# GSM.net
KiCad netlist of a schematic drawn in Altium Designer
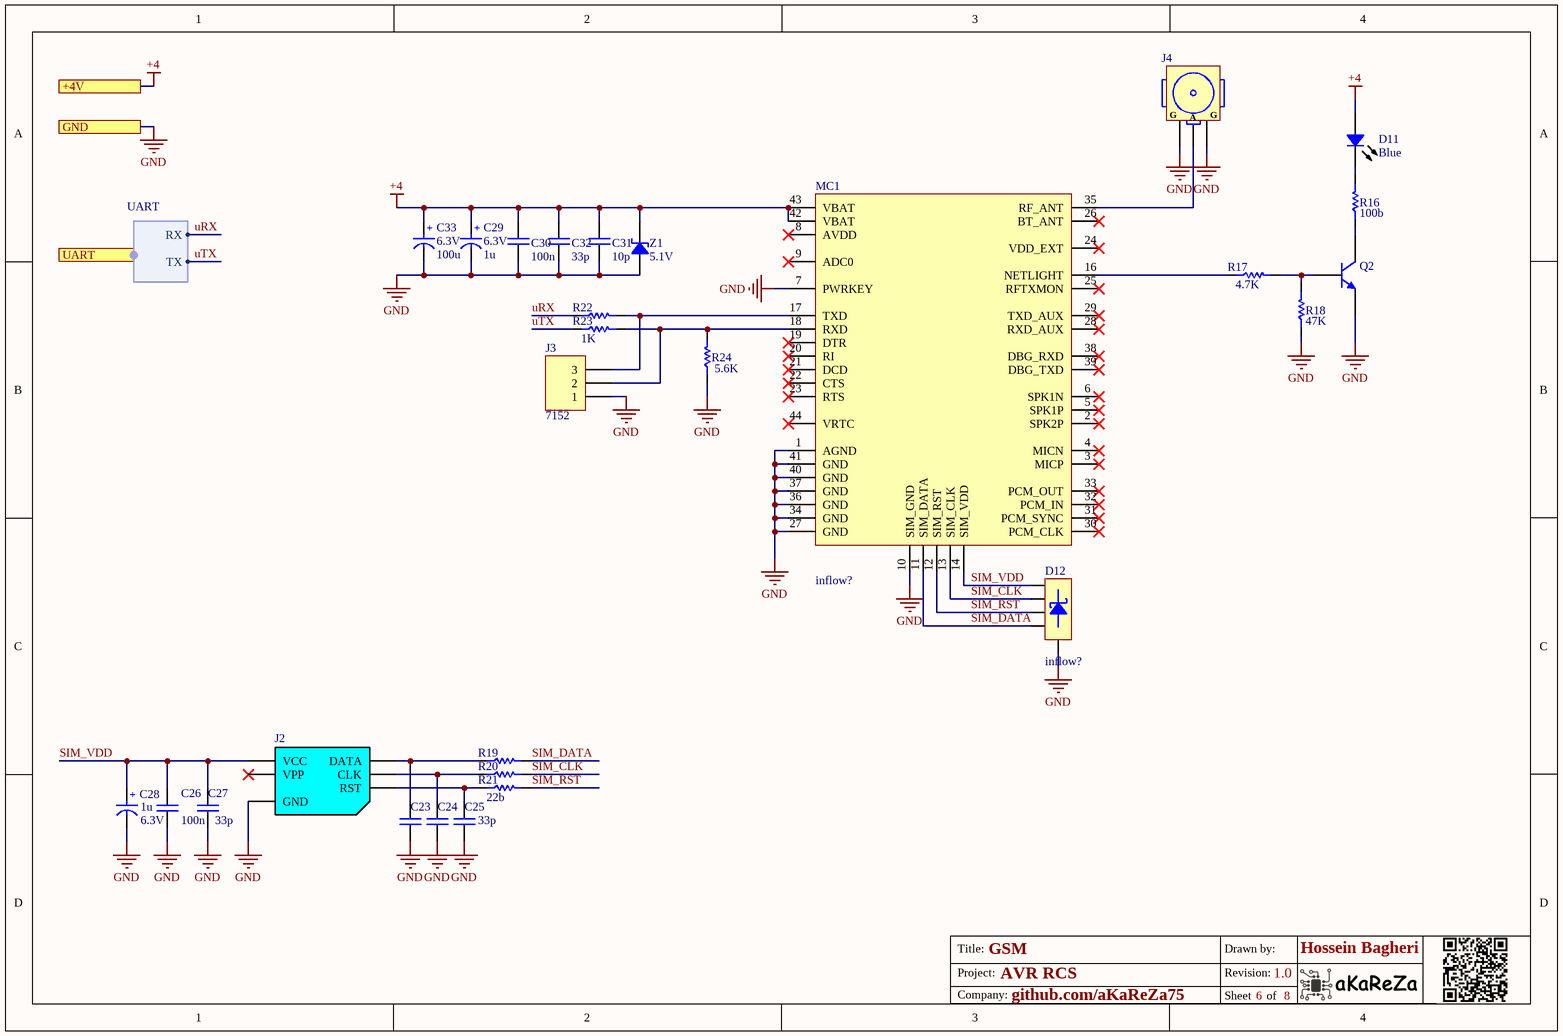
[diagram p0: GSM.SchDoc]

(export (version "E")
  (design (tool "Eeschema 10.0.6"))
  (components
    (comp (ref "C23")
      (value "33p")
      (footprint "CAP 0805/2012")
      (description "Bipolar ceramic capacitor SMD")
      (libsource (lib "aKaReZa") (part "Cap_Multi_SMD_0805"))
    )
    (comp (ref "C24")
      (value "33p")
      (footprint "CAP 0805/2012")
      (description "Bipolar ceramic capacitor SMD")
      (libsource (lib "aKaReZa") (part "Cap_Multi_SMD_0805"))
    )
    (comp (ref "C25")
      (value "33p")
      (footprint "CAP 0805/2012")
      (description "Bipolar ceramic capacitor SMD")
      (libsource (lib "aKaReZa") (part "Cap_Multi_SMD_0805"))
    )
    (comp (ref "C26")
      (value "100n")
      (footprint "CAP 0805/2012")
      (description "Bipolar ceramic capacitor SMD")
      (libsource (lib "aKaReZa") (part "Cap_Multi_SMD_100nF_0805"))
    )
    (comp (ref "C27")
      (value "33p")
      (footprint "CAP 0805/2012")
      (description "Bipolar ceramic capacitor SMD")
      (libsource (lib "aKaReZa") (part "Cap_Multi_SMD_0805"))
    )
    (comp (ref "C28")
      (value "1u")
      (footprint "SMT_C_Tantalum_A")
      (description "Tantalum Capacitor,TAJ Series-SMD")
      (fields (field (name "RATING") "6.3V"))
      (libsource (lib "aKaReZa") (part "Cap_Tantalum"))
    )
    (comp (ref "C29")
      (value "1u")
      (footprint "SMT_C_Tantalum_A")
      (description "Tantalum Capacitor,TAJ Series-SMD")
      (fields (field (name "RATING") "6.3V"))
      (libsource (lib "aKaReZa") (part "Cap_Tantalum"))
    )
    (comp (ref "C30")
      (value "100n")
      (footprint "CAP 1206/3216")
      (description "Bipolar ceramic capacitor SMD")
      (libsource (lib "aKaReZa") (part "Cap_Multi_SMD_100nF_1206"))
    )
    (comp (ref "C31")
      (value "10p")
      (footprint "CAP 1206/3216")
      (description "Bipolar ceramic capacitor SMD")
      (libsource (lib "aKaReZa") (part "Cap_Multi_SMD_1206"))
    )
    (comp (ref "C32")
      (value "33p")
      (footprint "CAP 1206/3216")
      (description "Bipolar ceramic capacitor SMD")
      (libsource (lib "aKaReZa") (part "Cap_Multi_SMD_1206"))
    )
    (comp (ref "C33")
      (value "100u")
      (footprint "SMT_C_Tantalum_C")
      (description "Tantalum Capacitor,TAJ Series-SMD")
      (fields (field (name "RATING") "6.3V"))
      (libsource (lib "aKaReZa") (part "Cap_Tantalum"))
    )
    (comp (ref "D11")
      (value "Blue")
      (footprint "LED 0805/2012 BLUE")
      (description "LED")
      (fields (field (name "VALIDATION") "Valid"))
      (libsource (lib "aKaReZa") (part "Semi_LED_SMD"))
    )
    (comp (ref "D12")
      (value "SMF-05")
      (footprint "SC70-5_N")
      (description "TVS Diode Array")
      (fields (field (name "INFLOW") "inflow?") (field (name "VALIDATION") "Valid"))
      (libsource (lib "aKaReZa") (part "Semi_Diod_TVS_SMF05"))
    )
    (comp (ref "J2")
      (value "6'Pin")
      (footprint "GCT_SIM8051_Plastik")
      (description "Nano SimCard Holder 6P")
      (fields (field (name "VALIDATION") "Valid"))
      (libsource (lib "aKaReZa") (part "Con_Socket_SimCard_1"))
    )
    (comp (ref "J3")
      (value "3")
      (footprint "HDR_THT_3M_2.54mm")
      (description "Header, single row, 3 pin")
      (fields (field (name "INFLOW") "7152") (field (name "VALIDATION") "NT"))
      (libsource (lib "aKaReZa") (part "Con_MPH_3x1_V_THT_2.54"))
    )
    (comp (ref "J4") (value "U.FL") (footprint "IPEX-3x3mm") (libsource (lib "aKaReZa") (part "Con_RF_U.FL")))
    (comp (ref "MC1")
      (value "M66")
      (footprint "m66")
      (description "Quectel GSM/GPRS Module")
      (fields (field (name "INFLOW") "inflow?") (field (name "VALIDATION") "Valid"))
      (libsource (lib "aKaReZa") (part "ModSen_Com_M66"))
    )
    (comp (ref "Q2")
      (value "NPN")
      (footprint "SOT23_N")
      (description "NPN General purpose Transistor")
      (fields (field (name "VALIDATION") "Valid"))
      (libsource (lib "aKaReZa") (part "Semi_BJT_BC817"))
    )
    (comp (ref "R16")
      (value "100b")
      (footprint "RES 0805 (2012X06L)")
      (description "Resistor")
      (libsource (lib "aKaReZa") (part "Res_SMD_0805"))
    )
    (comp (ref "R17")
      (value "4.7K")
      (footprint "RES 0805 (2012X06L)")
      (description "Resistor")
      (libsource (lib "aKaReZa") (part "Res_SMD_0805"))
    )
    (comp (ref "R18")
      (value "47K")
      (footprint "RES 0805 (2012X06L)")
      (description "Resistor")
      (libsource (lib "aKaReZa") (part "Res_SMD_0805"))
    )
    (comp (ref "R19")
      (value "22b")
      (footprint "RES 0805 (2012X06L)")
      (description "Resistor")
      (libsource (lib "aKaReZa") (part "Res_SMD_0805"))
    )
    (comp (ref "R20")
      (value "22b")
      (footprint "RES 0805 (2012X06L)")
      (description "Resistor")
      (libsource (lib "aKaReZa") (part "Res_SMD_0805"))
    )
    (comp (ref "R21")
      (value "22b")
      (footprint "RES 0805 (2012X06L)")
      (description "Resistor")
      (libsource (lib "aKaReZa") (part "Res_SMD_0805"))
    )
    (comp (ref "R22")
      (value "1K")
      (footprint "RES 0805 (2012X06L)")
      (description "Resistor")
      (libsource (lib "aKaReZa") (part "Res_SMD_0805"))
    )
    (comp (ref "R23")
      (value "1K")
      (footprint "RES 0805 (2012X06L)")
      (description "Resistor")
      (libsource (lib "aKaReZa") (part "Res_SMD_0805"))
    )
    (comp (ref "R24")
      (value "5.6K")
      (footprint "RES 0805 (2012X06L)")
      (description "Resistor")
      (libsource (lib "aKaReZa") (part "Res_SMD_0805"))
    )
    (comp (ref "Z1")
      (value "5.1V")
      (footprint "SOD80, LL-34")
      (description "Zener Diode")
      (libsource (lib "aKaReZa") (part "Semi_Diod_Zener_SMD"))
    )
  )
  (nets
    (net (code "2") (name "+4") (class "Default")
      (node (ref "C29") (pin "1") (pinfunction "+_1") (pintype "passive"))
      (node (ref "C30") (pin "1") (pinfunction "1_1") (pintype "passive"))
      (node (ref "C31") (pin "1") (pinfunction "1_1") (pintype "passive"))
      (node (ref "C32") (pin "1") (pinfunction "1_1") (pintype "passive"))
      (node (ref "C33") (pin "1") (pinfunction "+_1") (pintype "passive"))
      (node (ref "D11") (pin "1") (pinfunction "1_1") (pintype "passive"))
      (node (ref "MC1") (pin "42") (pinfunction "VBAT_42") (pintype "passive"))
      (node (ref "MC1") (pin "43") (pinfunction "VBAT_43") (pintype "passive"))
      (node (ref "Z1") (pin "2") (pinfunction "2_2") (pintype "passive"))
    )
    (net (code "3") (name "/SIM_CLK") (class "Default")
      (node (ref "D12") (pin "3") (pinfunction "K_3") (pintype "passive"))
      (node (ref "MC1") (pin "13") (pinfunction "SIM_CLK_13") (pintype "passive"))
      (node (ref "R20") (pin "2") (pinfunction "2_2") (pintype "passive"))
    )
    (net (code "4") (name "/SIM_DATA") (class "Default")
      (node (ref "D12") (pin "5") (pinfunction "K_5") (pintype "passive"))
      (node (ref "MC1") (pin "11") (pinfunction "SIM_DATA_11") (pintype "passive"))
      (node (ref "R19") (pin "2") (pinfunction "2_2") (pintype "passive"))
    )
    (net (code "5") (name "/SIM_RST") (class "Default")
      (node (ref "D12") (pin "4") (pinfunction "K_4") (pintype "passive"))
      (node (ref "MC1") (pin "12") (pinfunction "SIM_RST_12") (pintype "passive"))
      (node (ref "R21") (pin "2") (pinfunction "2_2") (pintype "passive"))
    )
    (net (code "6") (name "/SIM_VDD") (class "Default")
      (node (ref "C26") (pin "1") (pinfunction "1_1") (pintype "passive"))
      (node (ref "C27") (pin "1") (pinfunction "1_1") (pintype "passive"))
      (node (ref "C28") (pin "1") (pinfunction "+_1") (pintype "passive"))
      (node (ref "D12") (pin "1") (pinfunction "K_1") (pintype "passive"))
      (node (ref "J2") (pin "1") (pinfunction "VCC_1") (pintype "passive"))
      (node (ref "MC1") (pin "14") (pinfunction "SIM_VDD_14") (pintype "passive"))
    )
    (net (code "7") (name "/uRX") (class "Default")
      (node (ref "R22") (pin "1") (pinfunction "1_1") (pintype "passive"))
    )
    (net (code "8") (name "/uTX") (class "Default")
      (node (ref "R23") (pin "1") (pinfunction "1_1") (pintype "passive"))
    )
    (net (code "10") (name "GND") (class "Default")
      (node (ref "C23") (pin "2") (pinfunction "2_2") (pintype "passive"))
      (node (ref "C24") (pin "2") (pinfunction "2_2") (pintype "passive"))
      (node (ref "C25") (pin "2") (pinfunction "2_2") (pintype "passive"))
      (node (ref "C26") (pin "2") (pinfunction "2_2") (pintype "passive"))
      (node (ref "C27") (pin "2") (pinfunction "2_2") (pintype "passive"))
      (node (ref "C28") (pin "2") (pinfunction "-_2") (pintype "passive"))
      (node (ref "C29") (pin "2") (pinfunction "-_2") (pintype "passive"))
      (node (ref "C30") (pin "2") (pinfunction "2_2") (pintype "passive"))
      (node (ref "C31") (pin "2") (pinfunction "2_2") (pintype "passive"))
      (node (ref "C32") (pin "2") (pinfunction "2_2") (pintype "passive"))
      (node (ref "C33") (pin "2") (pinfunction "-_2") (pintype "passive"))
      (node (ref "D12") (pin "2") (pinfunction "K_2") (pintype "passive"))
      (node (ref "J2") (pin "5") (pinfunction "GND_5") (pintype "passive"))
      (node (ref "J3") (pin "1") (pinfunction "1_1") (pintype "passive"))
      (node (ref "J4") (pin "2") (pinfunction "G_2") (pintype "passive"))
      (node (ref "J4") (pin "3") (pinfunction "G_3") (pintype "passive"))
      (node (ref "MC1") (pin "1") (pinfunction "AGND_1") (pintype "passive"))
      (node (ref "MC1") (pin "10") (pinfunction "SIM_GND_10") (pintype "passive"))
      (node (ref "MC1") (pin "27") (pinfunction "GND_27") (pintype "passive"))
      (node (ref "MC1") (pin "34") (pinfunction "GND_34") (pintype "passive"))
      (node (ref "MC1") (pin "36") (pinfunction "GND_36") (pintype "passive"))
      (node (ref "MC1") (pin "37") (pinfunction "GND_37") (pintype "passive"))
      (node (ref "MC1") (pin "40") (pinfunction "GND_40") (pintype "passive"))
      (node (ref "MC1") (pin "41") (pinfunction "GND_41") (pintype "passive"))
      (node (ref "MC1") (pin "7") (pinfunction "PWRKEY_7") (pintype "passive"))
      (node (ref "Q2") (pin "2") (pinfunction "E_2") (pintype "passive"))
      (node (ref "R18") (pin "1") (pinfunction "1_1") (pintype "passive"))
      (node (ref "R24") (pin "1") (pinfunction "1_1") (pintype "passive"))
      (node (ref "Z1") (pin "1") (pinfunction "1_1") (pintype "passive"))
    )
    (net (code "11") (name "Net-(D11-Pad2)") (class "Default")
      (node (ref "D11") (pin "2") (pinfunction "2_2") (pintype "passive"))
      (node (ref "R16") (pin "2") (pinfunction "2_2") (pintype "passive"))
    )
    (net (code "12") (name "Net-(J2-CLK)") (class "Default")
      (node (ref "C24") (pin "1") (pinfunction "1_1") (pintype "passive"))
      (node (ref "J2") (pin "3") (pinfunction "CLK_3") (pintype "passive"))
      (node (ref "R20") (pin "1") (pinfunction "1_1") (pintype "passive"))
    )
    (net (code "13") (name "Net-(J2-DATA)") (class "Default")
      (node (ref "C23") (pin "1") (pinfunction "1_1") (pintype "passive"))
      (node (ref "J2") (pin "4") (pinfunction "DATA_4") (pintype "passive"))
      (node (ref "R19") (pin "1") (pinfunction "1_1") (pintype "passive"))
    )
    (net (code "14") (name "Net-(J2-RST)") (class "Default")
      (node (ref "C25") (pin "1") (pinfunction "1_1") (pintype "passive"))
      (node (ref "J2") (pin "2") (pinfunction "RST_2") (pintype "passive"))
      (node (ref "R21") (pin "1") (pinfunction "1_1") (pintype "passive"))
    )
    (net (code "15") (name "Net-(J4-A)") (class "Default")
      (node (ref "J4") (pin "1") (pinfunction "A_1") (pintype "passive"))
      (node (ref "MC1") (pin "35") (pinfunction "RF_ANT_35") (pintype "passive"))
    )
    (net (code "16") (name "Net-(MC1-NETLIGHT)") (class "Default")
      (node (ref "MC1") (pin "16") (pinfunction "NETLIGHT_16") (pintype "passive"))
      (node (ref "R17") (pin "1") (pinfunction "1_1") (pintype "passive"))
    )
    (net (code "17") (name "Net-(MC1-RXD)") (class "Default")
      (node (ref "J3") (pin "2") (pinfunction "2_2") (pintype "passive"))
      (node (ref "MC1") (pin "18") (pinfunction "RXD_18") (pintype "passive"))
      (node (ref "R23") (pin "2") (pinfunction "2_2") (pintype "passive"))
      (node (ref "R24") (pin "2") (pinfunction "2_2") (pintype "passive"))
    )
    (net (code "18") (name "Net-(MC1-TXD)") (class "Default")
      (node (ref "J3") (pin "3") (pinfunction "3_3") (pintype "passive"))
      (node (ref "MC1") (pin "17") (pinfunction "TXD_17") (pintype "passive"))
      (node (ref "R22") (pin "2") (pinfunction "2_2") (pintype "passive"))
    )
    (net (code "19") (name "Net-(Q2-B)") (class "Default")
      (node (ref "Q2") (pin "1") (pinfunction "B_1") (pintype "passive"))
      (node (ref "R17") (pin "2") (pinfunction "2_2") (pintype "passive"))
      (node (ref "R18") (pin "2") (pinfunction "2_2") (pintype "passive"))
    )
    (net (code "20") (name "Net-(Q2-C)") (class "Default")
      (node (ref "Q2") (pin "3") (pinfunction "C_3") (pintype "passive"))
      (node (ref "R16") (pin "1") (pinfunction "1_1") (pintype "passive"))
    )
    (net (code "21") (name "unconnected-(J2-VPP-Pad6)") (class "Default")
      (node (ref "J2") (pin "6") (pinfunction "VPP_6") (pintype "passive+no_connect"))
    )
    (net (code "22") (name "unconnected-(MC1-ADC0-Pad9)") (class "Default")
      (node (ref "MC1") (pin "9") (pinfunction "ADC0_9") (pintype "passive+no_connect"))
    )
    (net (code "23") (name "unconnected-(MC1-AVDD-Pad8)") (class "Default")
      (node (ref "MC1") (pin "8") (pinfunction "AVDD_8") (pintype "passive+no_connect"))
    )
    (net (code "24") (name "unconnected-(MC1-BT_ANT-Pad26)") (class "Default")
      (node (ref "MC1") (pin "26") (pinfunction "BT_ANT_26") (pintype "passive+no_connect"))
    )
    (net (code "25") (name "unconnected-(MC1-CTS-Pad22)") (class "Default")
      (node (ref "MC1") (pin "22") (pinfunction "CTS_22") (pintype "passive+no_connect"))
    )
    (net (code "26") (name "unconnected-(MC1-DBG_RXD-Pad38)") (class "Default")
      (node (ref "MC1") (pin "38") (pinfunction "DBG_RXD_38") (pintype "passive+no_connect"))
    )
    (net (code "27") (name "unconnected-(MC1-DBG_TXD-Pad39)") (class "Default")
      (node (ref "MC1") (pin "39") (pinfunction "DBG_TXD_39") (pintype "passive+no_connect"))
    )
    (net (code "28") (name "unconnected-(MC1-DCD-Pad21)") (class "Default")
      (node (ref "MC1") (pin "21") (pinfunction "DCD_21") (pintype "passive+no_connect"))
    )
    (net (code "29") (name "unconnected-(MC1-DTR-Pad19)") (class "Default")
      (node (ref "MC1") (pin "19") (pinfunction "DTR_19") (pintype "passive+no_connect"))
    )
    (net (code "30") (name "unconnected-(MC1-MICN-Pad4)") (class "Default")
      (node (ref "MC1") (pin "4") (pinfunction "MICN_4") (pintype "passive+no_connect"))
    )
    (net (code "31") (name "unconnected-(MC1-MICP-Pad3)") (class "Default")
      (node (ref "MC1") (pin "3") (pinfunction "MICP_3") (pintype "passive+no_connect"))
    )
    (net (code "32") (name "unconnected-(MC1-PCM_CLK-Pad30)") (class "Default")
      (node (ref "MC1") (pin "30") (pinfunction "PCM_CLK_30") (pintype "passive+no_connect"))
    )
    (net (code "33") (name "unconnected-(MC1-PCM_IN-Pad32)") (class "Default")
      (node (ref "MC1") (pin "32") (pinfunction "PCM_IN_32") (pintype "passive+no_connect"))
    )
    (net (code "34") (name "unconnected-(MC1-PCM_OUT-Pad33)") (class "Default")
      (node (ref "MC1") (pin "33") (pinfunction "PCM_OUT_33") (pintype "passive+no_connect"))
    )
    (net (code "35") (name "unconnected-(MC1-PCM_SYNC-Pad31)") (class "Default")
      (node (ref "MC1") (pin "31") (pinfunction "PCM_SYNC_31") (pintype "passive+no_connect"))
    )
    (net (code "36") (name "unconnected-(MC1-RFTXMON-Pad25)") (class "Default")
      (node (ref "MC1") (pin "25") (pinfunction "RFTXMON_25") (pintype "passive+no_connect"))
    )
    (net (code "37") (name "unconnected-(MC1-RI-Pad20)") (class "Default")
      (node (ref "MC1") (pin "20") (pinfunction "RI_20") (pintype "passive+no_connect"))
    )
    (net (code "38") (name "unconnected-(MC1-RTS-Pad23)") (class "Default")
      (node (ref "MC1") (pin "23") (pinfunction "RTS_23") (pintype "passive+no_connect"))
    )
    (net (code "39") (name "unconnected-(MC1-RXD_AUX-Pad28)") (class "Default")
      (node (ref "MC1") (pin "28") (pinfunction "RXD_AUX_28") (pintype "passive+no_connect"))
    )
    (net (code "40") (name "unconnected-(MC1-SPK1N-Pad6)") (class "Default")
      (node (ref "MC1") (pin "6") (pinfunction "SPK1N_6") (pintype "passive+no_connect"))
    )
    (net (code "41") (name "unconnected-(MC1-SPK1P-Pad5)") (class "Default")
      (node (ref "MC1") (pin "5") (pinfunction "SPK1P_5") (pintype "passive+no_connect"))
    )
    (net (code "42") (name "unconnected-(MC1-SPK2P-Pad2)") (class "Default")
      (node (ref "MC1") (pin "2") (pinfunction "SPK2P_2") (pintype "passive+no_connect"))
    )
    (net (code "43") (name "unconnected-(MC1-TXD_AUX-Pad29)") (class "Default")
      (node (ref "MC1") (pin "29") (pinfunction "TXD_AUX_29") (pintype "passive+no_connect"))
    )
    (net (code "44") (name "unconnected-(MC1-VDD_EXT-Pad24)") (class "Default")
      (node (ref "MC1") (pin "24") (pinfunction "VDD_EXT_24") (pintype "passive+no_connect"))
    )
    (net (code "45") (name "unconnected-(MC1-VRTC-Pad44)") (class "Default")
      (node (ref "MC1") (pin "44") (pinfunction "VRTC_44") (pintype "passive+no_connect"))
    )
  )
)
